# relais_platine_v8.net
KiCad netlist of a schematic drawn in EAGLE
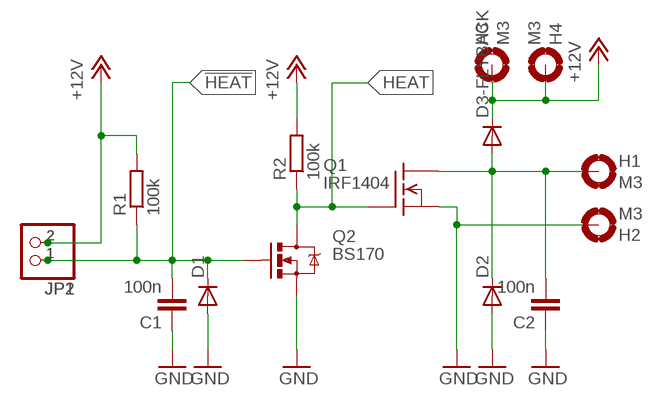
[diagram p0: schematic, sheet 1]

(export (version "E")
  (design (tool "Eeschema 10.0.6"))
  (components
    (comp (ref "C1")
      (value "100n")
      (footprint "eagle-import:C0805K")
      (libsource (lib "eagle-import") (part "C-EUC0805K"))
    )
    (comp (ref "C2")
      (value "100n")
      (footprint "eagle-import:C0805K")
      (libsource (lib "eagle-import") (part "C-EUC0805K"))
    )
    (comp (ref "D1")
      (value "DIODE-MINIMELF")
      (footprint "eagle-import:MINIMELF")
      (libsource (lib "eagle-import") (part "DIODE-MINIMELF"))
    )
    (comp (ref "D2")
      (value "DIODE-MINIMELF")
      (footprint "eagle-import:MINIMELF")
      (libsource (lib "eagle-import") (part "DIODE-MINIMELF"))
    )
    (comp (ref "D3-FLYBACK")
      (value "DIODE-MINIMELF")
      (footprint "eagle-import:MINIMELF")
      (libsource (lib "eagle-import") (part "DIODE-MINIMELF"))
    )
    (comp (ref "H1")
      (value "M3")
      (footprint "eagle-import:3,0-PAD")
      (libsource (lib "eagle-import") (part "MOUNT-PAD-ROUND3.0"))
    )
    (comp (ref "H2")
      (value "M3")
      (footprint "eagle-import:3,0-PAD")
      (libsource (lib "eagle-import") (part "MOUNT-PAD-ROUND3.0"))
    )
    (comp (ref "H3")
      (value "M3")
      (footprint "eagle-import:3,0-PAD")
      (libsource (lib "eagle-import") (part "MOUNT-PAD-ROUND3.0"))
    )
    (comp (ref "H4")
      (value "M3")
      (footprint "eagle-import:3,0-PAD")
      (libsource (lib "eagle-import") (part "MOUNT-PAD-ROUND3.0"))
    )
    (comp (ref "JP1")
      (value "PINHD-1X2")
      (footprint "eagle-import:1X02")
      (libsource (lib "eagle-import") (part "PINHD-1X2"))
    )
    (comp (ref "JP2")
      (value "PINHD-1X2/90")
      (footprint "eagle-import:1X02_90")
      (libsource (lib "eagle-import") (part "PINHD-1X2/90"))
    )
    (comp (ref "Q1")
      (value "IRF1404")
      (footprint "eagle-import:TO220")
      (libsource (lib "eagle-import") (part "IRF540"))
    )
    (comp (ref "Q2")
      (value "BS170")
      (footprint "eagle-import:SOT23-3")
      (libsource (lib "eagle-import") (part "MOSFET-NCHANNELBSS123LT1G"))
    )
    (comp (ref "R1")
      (value "100k")
      (footprint "eagle-import:M0805")
      (libsource (lib "eagle-import") (part "R-EU_M0805"))
    )
    (comp (ref "R2")
      (value "100k")
      (footprint "eagle-import:M0805")
      (libsource (lib "eagle-import") (part "R-EU_M0805"))
    )
  )
  (nets
    (net (code "1") (name "+12V") (class "Default")
      (node (ref "D3-FLYBACK") (pin "C") (pinfunction "C_C") (pintype "passive"))
      (node (ref "H3") (pin "B3,0") (pinfunction "MOUNT_B3,0") (pintype "passive"))
      (node (ref "H4") (pin "B3,0") (pinfunction "MOUNT_B3,0") (pintype "passive"))
      (node (ref "JP1") (pin "2") (pinfunction "2_2") (pintype "passive"))
      (node (ref "JP2") (pin "2") (pinfunction "2_2") (pintype "passive"))
      (node (ref "R1") (pin "2") (pinfunction "2_2") (pintype "passive"))
      (node (ref "R2") (pin "2") (pinfunction "2_2") (pintype "passive"))
    )
    (net (code "2") (name "/~{HEAT}") (class "Default")
      (node (ref "C1") (pin "2") (pinfunction "2_2") (pintype "passive"))
      (node (ref "D1") (pin "C") (pinfunction "C_C") (pintype "passive"))
      (node (ref "JP1") (pin "1") (pinfunction "1_1") (pintype "passive"))
      (node (ref "JP2") (pin "1") (pinfunction "1_1") (pintype "passive"))
      (node (ref "Q2") (pin "1") (pinfunction "G_1") (pintype "passive"))
      (node (ref "R1") (pin "1") (pinfunction "1_1") (pintype "passive"))
    )
    (net (code "3") (name "GND") (class "Default")
      (node (ref "C1") (pin "1") (pinfunction "1_1") (pintype "passive"))
      (node (ref "C2") (pin "1") (pinfunction "1_1") (pintype "passive"))
      (node (ref "D1") (pin "A") (pinfunction "A_A") (pintype "passive"))
      (node (ref "D2") (pin "A") (pinfunction "A_A") (pintype "passive"))
      (node (ref "H2") (pin "B3,0") (pinfunction "MOUNT_B3,0") (pintype "passive"))
      (node (ref "Q1") (pin "3") (pinfunction "S_3") (pintype "passive"))
      (node (ref "Q2") (pin "2") (pinfunction "S_2") (pintype "passive"))
    )
    (net (code "4") (name "HEAT") (class "Default")
      (node (ref "Q1") (pin "1") (pinfunction "G_1") (pintype "passive"))
      (node (ref "Q2") (pin "3") (pinfunction "D_3") (pintype "passive"))
      (node (ref "R2") (pin "1") (pinfunction "1_1") (pintype "passive"))
    )
    (net (code "5") (name "Net-(H1-MOUNT)") (class "Default")
      (node (ref "C2") (pin "2") (pinfunction "2_2") (pintype "passive"))
      (node (ref "D2") (pin "C") (pinfunction "C_C") (pintype "passive"))
      (node (ref "D3-FLYBACK") (pin "A") (pinfunction "A_A") (pintype "passive"))
      (node (ref "H1") (pin "B3,0") (pinfunction "MOUNT_B3,0") (pintype "passive"))
      (node (ref "Q1") (pin "2") (pinfunction "D_2") (pintype "passive"))
    )
  )
)
